# ProPrj_usb_hub_v2_2026-04-01.net
KiCad netlist of a schematic drawn in EasyEDA Pro
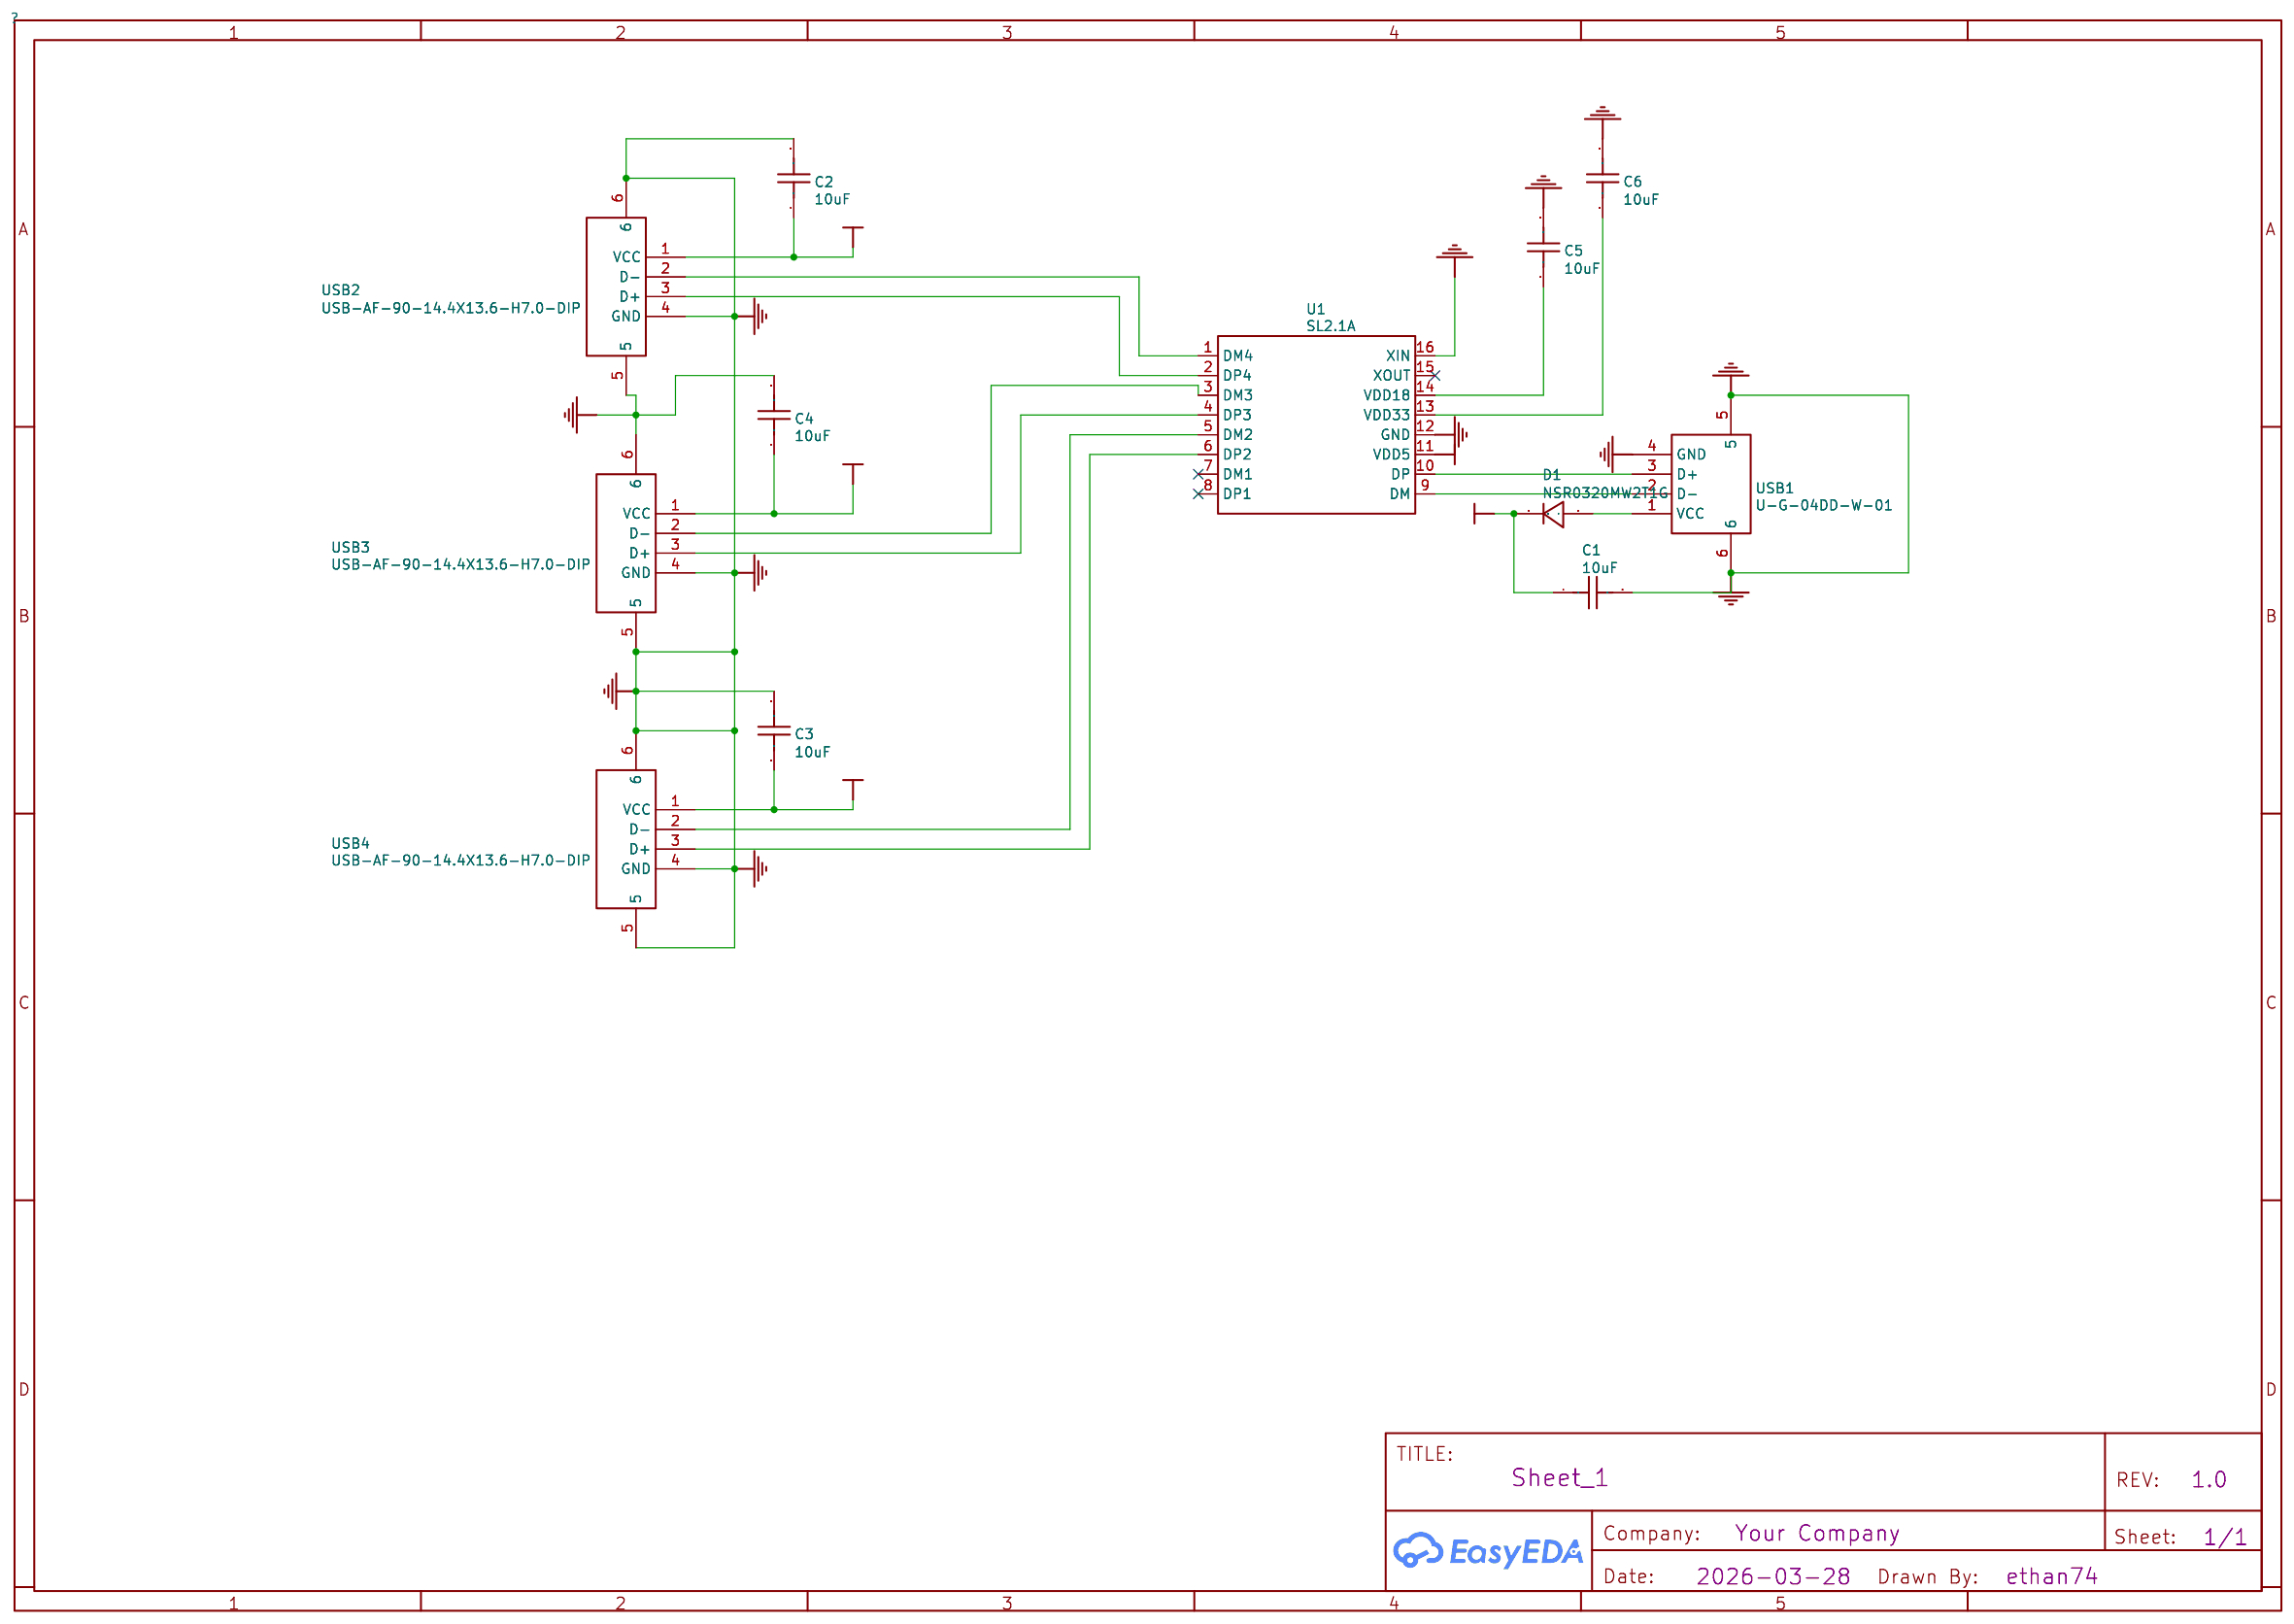
[diagram p0: schematic sheet]

(export (version "E")
  (design (tool "Eeschema 10.0.6"))
  (components
    (comp (ref "C1")
      (value "10uF")
      (footprint "easyedapro:C0603")
      (fields
        (field (name "Manufacturer Part") "CL10A106KP8NNNC")
        (field (name "Manufacturer") "SAMSUNG(三星)")
      )
      (libsource (lib "easyedapro") (part "10uF"))
    )
    (comp (ref "C2")
      (value "10uF")
      (footprint "easyedapro:C0603")
      (fields
        (field (name "Manufacturer Part") "CL10A106KP8NNNC")
        (field (name "Manufacturer") "SAMSUNG(三星)")
      )
      (libsource (lib "easyedapro") (part "10uF"))
    )
    (comp (ref "C3")
      (value "10uF")
      (footprint "easyedapro:C0603")
      (fields
        (field (name "Manufacturer Part") "CL10A106KP8NNNC")
        (field (name "Manufacturer") "SAMSUNG(三星)")
      )
      (libsource (lib "easyedapro") (part "10uF"))
    )
    (comp (ref "C4")
      (value "10uF")
      (footprint "easyedapro:C0603")
      (fields
        (field (name "Manufacturer Part") "CL10A106KP8NNNC")
        (field (name "Manufacturer") "SAMSUNG(三星)")
      )
      (libsource (lib "easyedapro") (part "10uF"))
    )
    (comp (ref "C5")
      (value "10uF")
      (footprint "easyedapro:C0603")
      (fields
        (field (name "Manufacturer Part") "CL10A106KP8NNNC")
        (field (name "Manufacturer") "SAMSUNG(三星)")
      )
      (libsource (lib "easyedapro") (part "10uF"))
    )
    (comp (ref "C6")
      (value "10uF")
      (footprint "easyedapro:C0603")
      (fields
        (field (name "Manufacturer Part") "CL10A106KP8NNNC")
        (field (name "Manufacturer") "SAMSUNG(三星)")
      )
      (libsource (lib "easyedapro") (part "10uF"))
    )
    (comp (ref "D1")
      (value "NSR0320MW2T1G")
      (footprint "easyedapro:SOD-323_L1.8-W1.3-LS2.5-RD")
      (fields (field (name "Manufacturer") "onsemi(安森美)"))
      (libsource (lib "easyedapro") (part "NSR0320MW2T1G"))
    )
    (comp (ref "U1")
      (value "SL2.1A")
      (footprint "easyedapro:SOP-16_L10.0-W3.9-P1.27-LS6.0-BL")
      (fields (field (name "Manufacturer") "CoreChips(和芯润德)") (field (name "Contributor") "LCSC"))
      (libsource (lib "easyedapro") (part "SL2.1A"))
    )
    (comp (ref "USB1")
      (value "U-G-04DD-W-01")
      (footprint "easyedapro:USB-A-TH_U-G-04WD-W-01")
      (fields (field (name "Manufacturer Part") "U-G-O4DD-W-1") (field (name "Manufacturer") "韩国韩荣"))
      (libsource (lib "easyedapro") (part "U-G-04DD-W-01"))
    )
    (comp (ref "USB2")
      (value "USB-AF-90-14.4X13.6-H7.0-DIP")
      (footprint "easyedapro:USB-A-TH_C46407")
      (fields
        (field (name "Manufacturer Part") "903-131A1011D10100")
        (field (name "Manufacturer") "精拓金")
        (field (name "Contributor") "LCSC")
      )
      (libsource (lib "easyedapro") (part "USB-AF-90-14.4X13.6-H7.0-DIP"))
    )
    (comp (ref "USB3")
      (value "USB-AF-90-14.4X13.6-H7.0-DIP")
      (footprint "easyedapro:USB-A-TH_C46407")
      (fields
        (field (name "Manufacturer Part") "903-131A1011D10100")
        (field (name "Manufacturer") "精拓金")
        (field (name "Contributor") "LCSC")
      )
      (libsource (lib "easyedapro") (part "USB-AF-90-14.4X13.6-H7.0-DIP"))
    )
    (comp (ref "USB4")
      (value "USB-AF-90-14.4X13.6-H7.0-DIP")
      (footprint "easyedapro:USB-A-TH_C46407")
      (fields
        (field (name "Manufacturer Part") "903-131A1011D10100")
        (field (name "Manufacturer") "精拓金")
        (field (name "Contributor") "LCSC")
      )
      (libsource (lib "easyedapro") (part "USB-AF-90-14.4X13.6-H7.0-DIP"))
    )
  )
  (nets
    (net (code "1") (name "+5V") (class "Default")
      (node (ref "C1") (pin "1") (pinfunction "1_1") (pintype "unspecified"))
      (node (ref "C2") (pin "1") (pinfunction "1_1") (pintype "unspecified"))
      (node (ref "C3") (pin "1") (pinfunction "1_1") (pintype "unspecified"))
      (node (ref "C4") (pin "1") (pinfunction "1_1") (pintype "unspecified"))
      (node (ref "D1") (pin "1") (pinfunction "C_1") (pintype "unspecified"))
      (node (ref "U1") (pin "11") (pinfunction "VDD5_11") (pintype "unspecified"))
      (node (ref "USB2") (pin "1") (pinfunction "VCC_1") (pintype "unspecified"))
      (node (ref "USB3") (pin "1") (pinfunction "VCC_1") (pintype "unspecified"))
      (node (ref "USB4") (pin "1") (pinfunction "VCC_1") (pintype "unspecified"))
    )
    (net (code "2") (name "GND") (class "Default")
      (node (ref "C1") (pin "2") (pinfunction "2_2") (pintype "unspecified"))
      (node (ref "C2") (pin "2") (pinfunction "2_2") (pintype "unspecified"))
      (node (ref "C3") (pin "2") (pinfunction "2_2") (pintype "unspecified"))
      (node (ref "C4") (pin "2") (pinfunction "2_2") (pintype "unspecified"))
      (node (ref "C5") (pin "2") (pinfunction "2_2") (pintype "unspecified"))
      (node (ref "C6") (pin "2") (pinfunction "2_2") (pintype "unspecified"))
      (node (ref "U1") (pin "12") (pinfunction "GND_12") (pintype "unspecified"))
      (node (ref "U1") (pin "16") (pinfunction "XIN_16") (pintype "unspecified"))
      (node (ref "USB1") (pin "4") (pinfunction "GND_4") (pintype "unspecified"))
      (node (ref "USB1") (pin "5") (pinfunction "5_5") (pintype "unspecified"))
      (node (ref "USB1") (pin "6") (pinfunction "6_6") (pintype "unspecified"))
      (node (ref "USB2") (pin "4") (pinfunction "GND_4") (pintype "unspecified"))
      (node (ref "USB2") (pin "5") (pinfunction "5_5") (pintype "unspecified"))
      (node (ref "USB2") (pin "6") (pinfunction "6_6") (pintype "unspecified"))
      (node (ref "USB3") (pin "4") (pinfunction "GND_4") (pintype "unspecified"))
      (node (ref "USB3") (pin "5") (pinfunction "5_5") (pintype "unspecified"))
      (node (ref "USB3") (pin "6") (pinfunction "6_6") (pintype "unspecified"))
      (node (ref "USB4") (pin "4") (pinfunction "GND_4") (pintype "unspecified"))
      (node (ref "USB4") (pin "5") (pinfunction "5_5") (pintype "unspecified"))
      (node (ref "USB4") (pin "6") (pinfunction "6_6") (pintype "unspecified"))
    )
    (net (code "3") (name "Net-(D1-A)") (class "Default")
      (node (ref "D1") (pin "2") (pinfunction "A_2") (pintype "unspecified"))
      (node (ref "USB1") (pin "1") (pinfunction "VCC_1") (pintype "unspecified"))
    )
    (net (code "4") (name "Net-(U1-DM)") (class "Default")
      (node (ref "U1") (pin "9") (pinfunction "DM_9") (pintype "unspecified"))
      (node (ref "USB1") (pin "2") (pinfunction "D-_2") (pintype "unspecified"))
    )
    (net (code "5") (name "Net-(U1-DM2)") (class "Default")
      (node (ref "U1") (pin "5") (pinfunction "DM2_5") (pintype "unspecified"))
      (node (ref "USB4") (pin "2") (pinfunction "D-_2") (pintype "unspecified"))
    )
    (net (code "6") (name "Net-(U1-DM3)") (class "Default")
      (node (ref "U1") (pin "3") (pinfunction "DM3_3") (pintype "unspecified"))
      (node (ref "USB3") (pin "2") (pinfunction "D-_2") (pintype "unspecified"))
    )
    (net (code "7") (name "Net-(U1-DM4)") (class "Default")
      (node (ref "U1") (pin "1") (pinfunction "DM4_1") (pintype "unspecified"))
      (node (ref "USB2") (pin "2") (pinfunction "D-_2") (pintype "unspecified"))
    )
    (net (code "8") (name "Net-(U1-DP)") (class "Default")
      (node (ref "U1") (pin "10") (pinfunction "DP_10") (pintype "unspecified"))
      (node (ref "USB1") (pin "3") (pinfunction "D+_3") (pintype "unspecified"))
    )
    (net (code "9") (name "Net-(U1-DP2)") (class "Default")
      (node (ref "U1") (pin "6") (pinfunction "DP2_6") (pintype "unspecified"))
      (node (ref "USB4") (pin "3") (pinfunction "D+_3") (pintype "unspecified"))
    )
    (net (code "10") (name "Net-(U1-DP3)") (class "Default")
      (node (ref "U1") (pin "4") (pinfunction "DP3_4") (pintype "unspecified"))
      (node (ref "USB3") (pin "3") (pinfunction "D+_3") (pintype "unspecified"))
    )
    (net (code "11") (name "Net-(U1-DP4)") (class "Default")
      (node (ref "U1") (pin "2") (pinfunction "DP4_2") (pintype "unspecified"))
      (node (ref "USB2") (pin "3") (pinfunction "D+_3") (pintype "unspecified"))
    )
    (net (code "12") (name "Net-(U1-VDD18)") (class "Default")
      (node (ref "C5") (pin "1") (pinfunction "1_1") (pintype "unspecified"))
      (node (ref "U1") (pin "14") (pinfunction "VDD18_14") (pintype "unspecified"))
    )
    (net (code "13") (name "Net-(U1-VDD33)") (class "Default")
      (node (ref "C6") (pin "1") (pinfunction "1_1") (pintype "unspecified"))
      (node (ref "U1") (pin "13") (pinfunction "VDD33_13") (pintype "unspecified"))
    )
    (net (code "14") (name "unconnected-(U1-DM1-Pad7)") (class "Default")
      (node (ref "U1") (pin "7") (pinfunction "DM1_7") (pintype "unspecified+no_connect"))
    )
    (net (code "15") (name "unconnected-(U1-DP1-Pad8)") (class "Default")
      (node (ref "U1") (pin "8") (pinfunction "DP1_8") (pintype "unspecified+no_connect"))
    )
    (net (code "16") (name "unconnected-(U1-XOUT-Pad15)") (class "Default")
      (node (ref "U1") (pin "15") (pinfunction "XOUT_15") (pintype "unspecified+no_connect"))
    )
  )
)
